# dac-v20_opamp.net
KiCad netlist of a schematic drawn in EAGLE
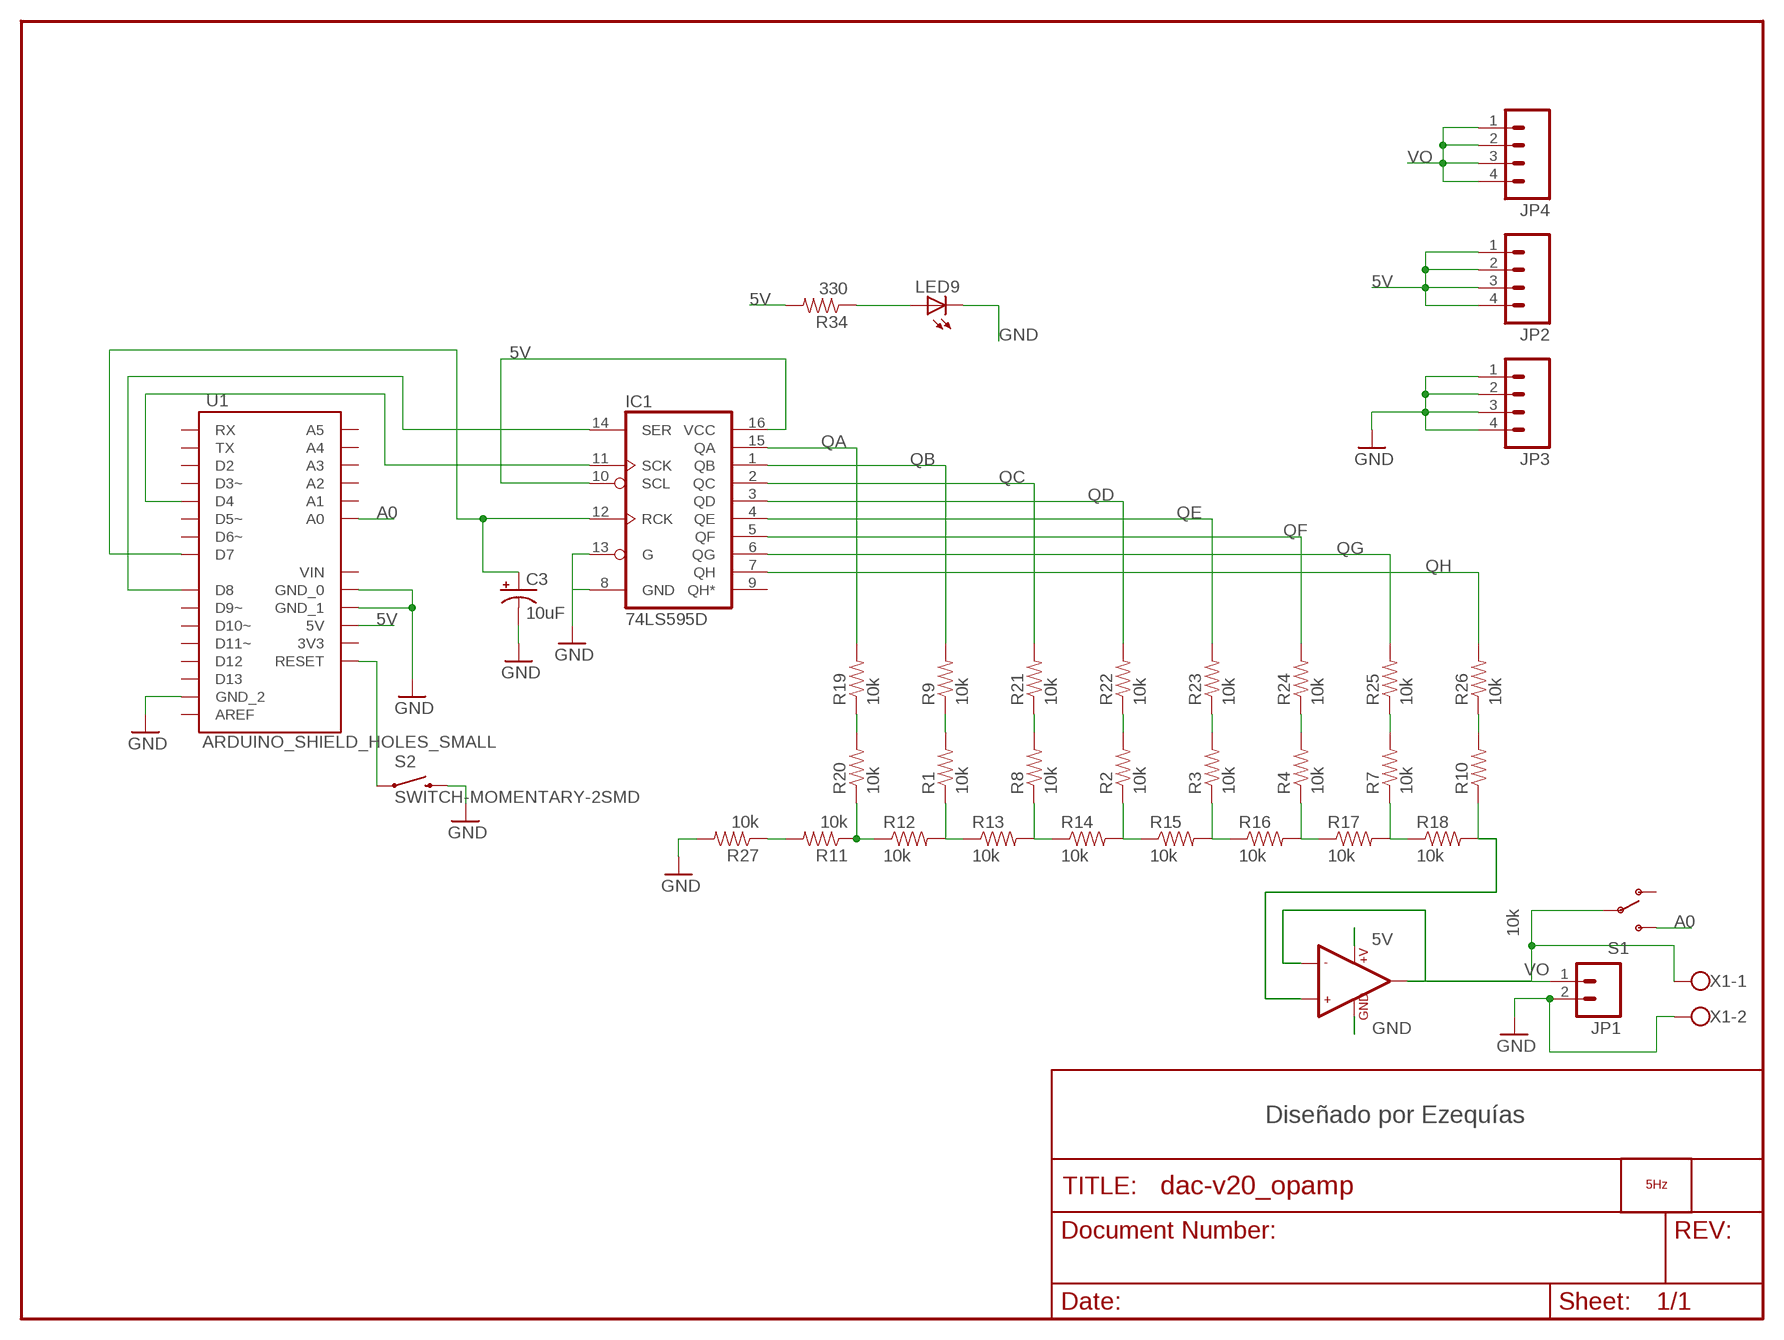
[diagram p0: schematic, sheet 1]

(export (version "E")
  (design (tool "Eeschema 10.0.6"))
  (components
    (comp (ref "C3")
      (value "10uF")
      (footprint "eagle-import:EIA3216")
      (libsource (lib "eagle-import") (part "CAP_POL1206"))
    )
    (comp (ref "IC1")
      (value "74LS595D")
      (footprint "eagle-import:SO16")
      (libsource (lib "eagle-import") (part "74595DLS"))
    )
    (comp (ref "JP1")
      (value "M02POLAR")
      (footprint "eagle-import:MOLEX-1X2")
      (libsource (lib "eagle-import") (part "M02POLAR"))
    )
    (comp (ref "JP2")
      (value "M04PTH")
      (footprint "eagle-import:1X04")
      (libsource (lib "eagle-import") (part "M04PTH"))
    )
    (comp (ref "JP3")
      (value "M04PTH")
      (footprint "eagle-import:1X04")
      (libsource (lib "eagle-import") (part "M04PTH"))
    )
    (comp (ref "JP4")
      (value "M04PTH")
      (footprint "eagle-import:1X04")
      (libsource (lib "eagle-import") (part "M04PTH"))
    )
    (comp (ref "LED9")
      (value "LED0603")
      (footprint "eagle-import:LED-0603")
      (libsource (lib "eagle-import") (part "LED0603"))
    )
    (comp (ref "LOGO2")
      (value "LOGO_5HZ_H_20MM")
      (footprint "eagle-import:5HZ_LOGO_H_20MM")
      (libsource (lib "eagle-import") (part "LOGO_5HZ_H_20MM"))
    )
    (comp (ref "R1")
      (value "10k")
      (footprint "eagle-import:0603-RES")
      (libsource (lib "eagle-import") (part "RESISTOR0603-RES"))
    )
    (comp (ref "R2")
      (value "10k")
      (footprint "eagle-import:0603-RES")
      (libsource (lib "eagle-import") (part "RESISTOR0603-RES"))
    )
    (comp (ref "R3")
      (value "10k")
      (footprint "eagle-import:0603-RES")
      (libsource (lib "eagle-import") (part "RESISTOR0603-RES"))
    )
    (comp (ref "R4")
      (value "10k")
      (footprint "eagle-import:0603-RES")
      (libsource (lib "eagle-import") (part "RESISTOR0603-RES"))
    )
    (comp (ref "R7")
      (value "10k")
      (footprint "eagle-import:0603-RES")
      (libsource (lib "eagle-import") (part "RESISTOR0603-RES"))
    )
    (comp (ref "R8")
      (value "10k")
      (footprint "eagle-import:0603-RES")
      (libsource (lib "eagle-import") (part "RESISTOR0603-RES"))
    )
    (comp (ref "R9")
      (value "10k")
      (footprint "eagle-import:0603-RES")
      (libsource (lib "eagle-import") (part "RESISTOR0603-RES"))
    )
    (comp (ref "R10")
      (value "10k")
      (footprint "eagle-import:0603-RES")
      (libsource (lib "eagle-import") (part "RESISTOR0603-RES"))
    )
    (comp (ref "R11")
      (value "10k")
      (footprint "eagle-import:0603-RES")
      (libsource (lib "eagle-import") (part "RESISTOR0603-RES"))
    )
    (comp (ref "R12")
      (value "10k")
      (footprint "eagle-import:0603-RES")
      (libsource (lib "eagle-import") (part "RESISTOR0603-RES"))
    )
    (comp (ref "R13")
      (value "10k")
      (footprint "eagle-import:0603-RES")
      (libsource (lib "eagle-import") (part "RESISTOR0603-RES"))
    )
    (comp (ref "R14")
      (value "10k")
      (footprint "eagle-import:0603-RES")
      (libsource (lib "eagle-import") (part "RESISTOR0603-RES"))
    )
    (comp (ref "R15")
      (value "10k")
      (footprint "eagle-import:0603-RES")
      (libsource (lib "eagle-import") (part "RESISTOR0603-RES"))
    )
    (comp (ref "R16")
      (value "10k")
      (footprint "eagle-import:0603-RES")
      (libsource (lib "eagle-import") (part "RESISTOR0603-RES"))
    )
    (comp (ref "R17")
      (value "10k")
      (footprint "eagle-import:0603-RES")
      (libsource (lib "eagle-import") (part "RESISTOR0603-RES"))
    )
    (comp (ref "R18")
      (value "10k")
      (footprint "eagle-import:0603-RES")
      (libsource (lib "eagle-import") (part "RESISTOR0603-RES"))
    )
    (comp (ref "R19")
      (value "10k")
      (footprint "eagle-import:0603-RES")
      (libsource (lib "eagle-import") (part "RESISTOR0603-RES"))
    )
    (comp (ref "R20")
      (value "10k")
      (footprint "eagle-import:0603-RES")
      (libsource (lib "eagle-import") (part "RESISTOR0603-RES"))
    )
    (comp (ref "R21")
      (value "10k")
      (footprint "eagle-import:0603-RES")
      (libsource (lib "eagle-import") (part "RESISTOR0603-RES"))
    )
    (comp (ref "R22")
      (value "10k")
      (footprint "eagle-import:0603-RES")
      (libsource (lib "eagle-import") (part "RESISTOR0603-RES"))
    )
    (comp (ref "R23")
      (value "10k")
      (footprint "eagle-import:0603-RES")
      (libsource (lib "eagle-import") (part "RESISTOR0603-RES"))
    )
    (comp (ref "R24")
      (value "10k")
      (footprint "eagle-import:0603-RES")
      (libsource (lib "eagle-import") (part "RESISTOR0603-RES"))
    )
    (comp (ref "R25")
      (value "10k")
      (footprint "eagle-import:0603-RES")
      (libsource (lib "eagle-import") (part "RESISTOR0603-RES"))
    )
    (comp (ref "R26")
      (value "10k")
      (footprint "eagle-import:0603-RES")
      (libsource (lib "eagle-import") (part "RESISTOR0603-RES"))
    )
    (comp (ref "R27")
      (value "10k")
      (footprint "eagle-import:0603-RES")
      (libsource (lib "eagle-import") (part "RESISTOR0603-RES"))
    )
    (comp (ref "R34")
      (value "330")
      (footprint "eagle-import:0603-RES")
      (libsource (lib "eagle-import") (part "RESISTOR0603-RES"))
    )
    (comp (ref "S1")
      (value "SWITCH-SPSTPTH")
      (footprint "eagle-import:SWITCH-SPDT")
      (libsource (lib "eagle-import") (part "SWITCH-SPSTPTH"))
    )
    (comp (ref "S2")
      (value "SWITCH-MOMENTARY-2SMD")
      (footprint "eagle-import:TACTILE_SWITCH_SMD")
      (libsource (lib "eagle-import") (part "SWITCH-MOMENTARY-2SMD"))
    )
    (comp (ref "U$1")
      (value "LMV358")
      (footprint "eagle-import:SO08")
      (libsource (lib "eagle-import") (part "LMV358"))
    )
    (comp (ref "U1")
      (value "ARDUINO_SHIELD_HOLES_SMALL")
      (footprint "eagle-import:UNO_SHIELD_SMALL_HOLES")
      (libsource (lib "eagle-import") (part "ARDUINO_SHIELD_HOLES_SMALL"))
    )
    (comp (ref "X1")
      (value "W237-102M2")
      (footprint "eagle-import:W237-102")
      (fields (field (name "MPN") "237-102"))
      (libsource (lib "eagle-import") (part "W237-102M2"))
    )
  )
  (nets
    (net (code "1") (name "/5V") (class "Default")
      (node (ref "IC1") (pin "10") (pinfunction "SCL_10") (pintype "input"))
      (node (ref "IC1") (pin "16") (pinfunction "VCC_16") (pintype "power_in"))
      (node (ref "JP2") (pin "1") (pinfunction "1_1") (pintype "passive"))
      (node (ref "JP2") (pin "2") (pinfunction "2_2") (pintype "passive"))
      (node (ref "JP2") (pin "3") (pinfunction "3_3") (pintype "passive"))
      (node (ref "JP2") (pin "4") (pinfunction "4_4") (pintype "passive"))
      (node (ref "R34") (pin "2") (pinfunction "2_2") (pintype "passive"))
      (node (ref "U$1") (pin "8") (pinfunction "+V_8") (pintype "power_in"))
      (node (ref "U1") (pin "5V") (pinfunction "5V_5V") (pintype "bidirectional"))
    )
    (net (code "2") (name "/A0") (class "Default")
      (node (ref "S1") (pin "3") (pinfunction "S_3") (pintype "passive"))
      (node (ref "U1") (pin "A0") (pinfunction "A0_A0") (pintype "bidirectional"))
    )
    (net (code "3") (name "/QA") (class "Default")
      (node (ref "IC1") (pin "15") (pinfunction "QA_15") (pintype "tri_state"))
      (node (ref "R19") (pin "2") (pinfunction "2_2") (pintype "passive"))
    )
    (net (code "4") (name "/QB") (class "Default")
      (node (ref "IC1") (pin "1") (pinfunction "QB_1") (pintype "tri_state"))
      (node (ref "R9") (pin "2") (pinfunction "2_2") (pintype "passive"))
    )
    (net (code "5") (name "/QC") (class "Default")
      (node (ref "IC1") (pin "2") (pinfunction "QC_2") (pintype "tri_state"))
      (node (ref "R21") (pin "2") (pinfunction "2_2") (pintype "passive"))
    )
    (net (code "6") (name "/QD") (class "Default")
      (node (ref "IC1") (pin "3") (pinfunction "QD_3") (pintype "tri_state"))
      (node (ref "R22") (pin "2") (pinfunction "2_2") (pintype "passive"))
    )
    (net (code "7") (name "/QE") (class "Default")
      (node (ref "IC1") (pin "4") (pinfunction "QE_4") (pintype "tri_state"))
      (node (ref "R23") (pin "2") (pinfunction "2_2") (pintype "passive"))
    )
    (net (code "8") (name "/QF") (class "Default")
      (node (ref "IC1") (pin "5") (pinfunction "QF_5") (pintype "tri_state"))
      (node (ref "R24") (pin "2") (pinfunction "2_2") (pintype "passive"))
    )
    (net (code "9") (name "/QG") (class "Default")
      (node (ref "IC1") (pin "6") (pinfunction "QG_6") (pintype "tri_state"))
      (node (ref "R25") (pin "2") (pinfunction "2_2") (pintype "passive"))
    )
    (net (code "10") (name "/QH") (class "Default")
      (node (ref "IC1") (pin "7") (pinfunction "QH_7") (pintype "tri_state"))
      (node (ref "R26") (pin "2") (pinfunction "2_2") (pintype "passive"))
    )
    (net (code "11") (name "/VO") (class "Default")
      (node (ref "JP1") (pin "1") (pinfunction "1_1") (pintype "passive"))
      (node (ref "JP4") (pin "1") (pinfunction "1_1") (pintype "passive"))
      (node (ref "JP4") (pin "2") (pinfunction "2_2") (pintype "passive"))
      (node (ref "JP4") (pin "3") (pinfunction "3_3") (pintype "passive"))
      (node (ref "JP4") (pin "4") (pinfunction "4_4") (pintype "passive"))
      (node (ref "S1") (pin "2") (pinfunction "P_2") (pintype "passive"))
      (node (ref "U$1") (pin "1") (pinfunction "OUT1_1") (pintype "output"))
      (node (ref "U$1") (pin "2") (pinfunction "-IN1_2") (pintype "input"))
      (node (ref "X1") (pin "1") (pinfunction "KL_1") (pintype "passive"))
    )
    (net (code "12") (name "GND") (class "Default")
      (node (ref "C3") (pin "C") (pinfunction "-_C") (pintype "passive"))
      (node (ref "IC1") (pin "13") (pinfunction "G_13") (pintype "input"))
      (node (ref "IC1") (pin "8") (pinfunction "GND_8") (pintype "power_in"))
      (node (ref "JP1") (pin "2") (pinfunction "2_2") (pintype "passive"))
      (node (ref "JP3") (pin "1") (pinfunction "1_1") (pintype "passive"))
      (node (ref "JP3") (pin "2") (pinfunction "2_2") (pintype "passive"))
      (node (ref "JP3") (pin "3") (pinfunction "3_3") (pintype "passive"))
      (node (ref "JP3") (pin "4") (pinfunction "4_4") (pintype "passive"))
      (node (ref "LED9") (pin "C") (pinfunction "C_C") (pintype "passive"))
      (node (ref "R27") (pin "2") (pinfunction "2_2") (pintype "passive"))
      (node (ref "S2") (pin "3") (pinfunction "2_3") (pintype "passive"))
      (node (ref "U$1") (pin "4") (pinfunction "GND_4") (pintype "power_in"))
      (node (ref "U1") (pin "GND_0") (pinfunction "GND_0_GND_0") (pintype "bidirectional"))
      (node (ref "U1") (pin "GND_1") (pinfunction "GND_1_GND_1") (pintype "bidirectional"))
      (node (ref "U1") (pin "GND_2") (pinfunction "GND_2_GND_2") (pintype "bidirectional"))
      (node (ref "X1") (pin "2") (pinfunction "KL_2") (pintype "passive"))
    )
    (net (code "13") (name "Net-(C3-+)") (class "Default")
      (node (ref "C3") (pin "A") (pinfunction "+_A") (pintype "passive"))
      (node (ref "IC1") (pin "12") (pinfunction "RCK_12") (pintype "input"))
      (node (ref "U1") (pin "D7") (pinfunction "D7_D7") (pintype "bidirectional"))
    )
    (net (code "14") (name "Net-(IC1-SCK)") (class "Default")
      (node (ref "IC1") (pin "11") (pinfunction "SCK_11") (pintype "input"))
      (node (ref "U1") (pin "D4") (pinfunction "D4_D4") (pintype "bidirectional"))
    )
    (net (code "15") (name "Net-(IC1-SER)") (class "Default")
      (node (ref "IC1") (pin "14") (pinfunction "SER_14") (pintype "input"))
      (node (ref "U1") (pin "D8") (pinfunction "D8_D8") (pintype "bidirectional"))
    )
    (net (code "16") (name "Net-(LED9-PadA)") (class "Default")
      (node (ref "LED9") (pin "A") (pinfunction "A_A") (pintype "passive"))
      (node (ref "R34") (pin "1") (pinfunction "1_1") (pintype "passive"))
    )
    (net (code "17") (name "Net-(R1-Pad1)") (class "Default")
      (node (ref "R1") (pin "1") (pinfunction "1_1") (pintype "passive"))
      (node (ref "R12") (pin "2") (pinfunction "2_2") (pintype "passive"))
      (node (ref "R13") (pin "1") (pinfunction "1_1") (pintype "passive"))
    )
    (net (code "18") (name "Net-(R1-Pad2)") (class "Default")
      (node (ref "R1") (pin "2") (pinfunction "2_2") (pintype "passive"))
      (node (ref "R9") (pin "1") (pinfunction "1_1") (pintype "passive"))
    )
    (net (code "19") (name "Net-(R2-Pad2)") (class "Default")
      (node (ref "R2") (pin "2") (pinfunction "2_2") (pintype "passive"))
      (node (ref "R22") (pin "1") (pinfunction "1_1") (pintype "passive"))
    )
    (net (code "20") (name "Net-(R10-Pad2)") (class "Default")
      (node (ref "R10") (pin "2") (pinfunction "2_2") (pintype "passive"))
      (node (ref "R26") (pin "1") (pinfunction "1_1") (pintype "passive"))
    )
    (net (code "21") (name "Net-(R11-Pad1)") (class "Default")
      (node (ref "R11") (pin "1") (pinfunction "1_1") (pintype "passive"))
      (node (ref "R12") (pin "1") (pinfunction "1_1") (pintype "passive"))
      (node (ref "R20") (pin "1") (pinfunction "1_1") (pintype "passive"))
    )
    (net (code "22") (name "Net-(R11-Pad2)") (class "Default")
      (node (ref "R11") (pin "2") (pinfunction "2_2") (pintype "passive"))
      (node (ref "R27") (pin "1") (pinfunction "1_1") (pintype "passive"))
    )
    (net (code "23") (name "Net-(R13-Pad2)") (class "Default")
      (node (ref "R13") (pin "2") (pinfunction "2_2") (pintype "passive"))
      (node (ref "R14") (pin "1") (pinfunction "1_1") (pintype "passive"))
      (node (ref "R8") (pin "1") (pinfunction "1_1") (pintype "passive"))
    )
    (net (code "24") (name "Net-(R14-Pad2)") (class "Default")
      (node (ref "R14") (pin "2") (pinfunction "2_2") (pintype "passive"))
      (node (ref "R15") (pin "1") (pinfunction "1_1") (pintype "passive"))
      (node (ref "R2") (pin "1") (pinfunction "1_1") (pintype "passive"))
    )
    (net (code "25") (name "Net-(R15-Pad2)") (class "Default")
      (node (ref "R15") (pin "2") (pinfunction "2_2") (pintype "passive"))
      (node (ref "R16") (pin "1") (pinfunction "1_1") (pintype "passive"))
      (node (ref "R3") (pin "1") (pinfunction "1_1") (pintype "passive"))
    )
    (net (code "26") (name "Net-(R16-Pad2)") (class "Default")
      (node (ref "R16") (pin "2") (pinfunction "2_2") (pintype "passive"))
      (node (ref "R17") (pin "1") (pinfunction "1_1") (pintype "passive"))
      (node (ref "R4") (pin "1") (pinfunction "1_1") (pintype "passive"))
    )
    (net (code "27") (name "Net-(R17-Pad2)") (class "Default")
      (node (ref "R17") (pin "2") (pinfunction "2_2") (pintype "passive"))
      (node (ref "R18") (pin "1") (pinfunction "1_1") (pintype "passive"))
      (node (ref "R7") (pin "1") (pinfunction "1_1") (pintype "passive"))
    )
    (net (code "28") (name "Net-(R19-Pad1)") (class "Default")
      (node (ref "R19") (pin "1") (pinfunction "1_1") (pintype "passive"))
      (node (ref "R20") (pin "2") (pinfunction "2_2") (pintype "passive"))
    )
    (net (code "29") (name "Net-(R21-Pad1)") (class "Default")
      (node (ref "R21") (pin "1") (pinfunction "1_1") (pintype "passive"))
      (node (ref "R8") (pin "2") (pinfunction "2_2") (pintype "passive"))
    )
    (net (code "30") (name "Net-(R23-Pad1)") (class "Default")
      (node (ref "R23") (pin "1") (pinfunction "1_1") (pintype "passive"))
      (node (ref "R3") (pin "2") (pinfunction "2_2") (pintype "passive"))
    )
    (net (code "31") (name "Net-(R24-Pad1)") (class "Default")
      (node (ref "R24") (pin "1") (pinfunction "1_1") (pintype "passive"))
      (node (ref "R4") (pin "2") (pinfunction "2_2") (pintype "passive"))
    )
    (net (code "32") (name "Net-(R25-Pad1)") (class "Default")
      (node (ref "R25") (pin "1") (pinfunction "1_1") (pintype "passive"))
      (node (ref "R7") (pin "2") (pinfunction "2_2") (pintype "passive"))
    )
    (net (code "33") (name "Net-(U$1A-+IN1)") (class "Default")
      (node (ref "R10") (pin "1") (pinfunction "1_1") (pintype "passive"))
      (node (ref "R18") (pin "2") (pinfunction "2_2") (pintype "passive"))
      (node (ref "U$1") (pin "3") (pinfunction "+IN1_3") (pintype "input"))
    )
    (net (code "34") (name "Net-(U1-RESET)") (class "Default")
      (node (ref "S2") (pin "1") (pinfunction "1_1") (pintype "passive"))
      (node (ref "U1") (pin "RES") (pinfunction "RESET_RES") (pintype "bidirectional"))
    )
    (net (code "35") (name "unconnected-(IC1-QH*-Pad9)") (class "Default")
      (node (ref "IC1") (pin "9") (pinfunction "QH*_9") (pintype "tri_state"))
    )
    (net (code "36") (name "unconnected-(S1-O-Pad1)") (class "Default")
      (node (ref "S1") (pin "1") (pinfunction "O_1") (pintype "passive"))
    )
    (net (code "37") (name "unconnected-(U1-3V3-Pad3.3V)") (class "Default")
      (node (ref "U1") (pin "3.3V") (pinfunction "3V3_3.3V") (pintype "bidirectional"))
    )
    (net (code "38") (name "unconnected-(U1-D3~{}-PadD3)") (class "Default")
      (node (ref "U1") (pin "D3") (pinfunction "D3~{}_D3") (pintype "bidirectional"))
    )
    (net (code "39") (name "unconnected-(U1-D5~{}-PadD5)") (class "Default")
      (node (ref "U1") (pin "D5") (pinfunction "D5~{}_D5") (pintype "bidirectional"))
    )
    (net (code "40") (name "unconnected-(U1-D6~{}-PadD6)") (class "Default")
      (node (ref "U1") (pin "D6") (pinfunction "D6~{}_D6") (pintype "bidirectional"))
    )
    (net (code "41") (name "unconnected-(U1-D9~{}-PadD9)") (class "Default")
      (node (ref "U1") (pin "D9") (pinfunction "D9~{}_D9") (pintype "bidirectional"))
    )
    (net (code "42") (name "unconnected-(U1-D10~{}-PadD10)") (class "Default")
      (node (ref "U1") (pin "D10") (pinfunction "D10~{}_D10") (pintype "bidirectional"))
    )
    (net (code "43") (name "unconnected-(U1-D11~{}-PadD11)") (class "Default")
      (node (ref "U1") (pin "D11") (pinfunction "D11~{}_D11") (pintype "bidirectional"))
    )
    (net (code "44") (name "unconnected-(U1-PadA1)") (class "Default")
      (node (ref "U1") (pin "A1") (pinfunction "A1_A1") (pintype "bidirectional"))
    )
    (net (code "45") (name "unconnected-(U1-PadA2)") (class "Default")
      (node (ref "U1") (pin "A2") (pinfunction "A2_A2") (pintype "bidirectional"))
    )
    (net (code "46") (name "unconnected-(U1-PadA3)") (class "Default")
      (node (ref "U1") (pin "A3") (pinfunction "A3_A3") (pintype "bidirectional"))
    )
    (net (code "47") (name "unconnected-(U1-PadA4)") (class "Default")
      (node (ref "U1") (pin "A4") (pinfunction "A4_A4") (pintype "bidirectional"))
    )
    (net (code "48") (name "unconnected-(U1-PadA5)") (class "Default")
      (node (ref "U1") (pin "A5") (pinfunction "A5_A5") (pintype "bidirectional"))
    )
    (net (code "49") (name "unconnected-(U1-PadAREF)") (class "Default")
      (node (ref "U1") (pin "AREF") (pinfunction "AREF_AREF") (pintype "bidirectional"))
    )
    (net (code "50") (name "unconnected-(U1-PadD2)") (class "Default")
      (node (ref "U1") (pin "D2") (pinfunction "D2_D2") (pintype "bidirectional"))
    )
    (net (code "51") (name "unconnected-(U1-PadD12)") (class "Default")
      (node (ref "U1") (pin "D12") (pinfunction "D12_D12") (pintype "bidirectional"))
    )
    (net (code "52") (name "unconnected-(U1-PadD13)") (class "Default")
      (node (ref "U1") (pin "D13") (pinfunction "D13_D13") (pintype "bidirectional"))
    )
    (net (code "53") (name "unconnected-(U1-PadRX)") (class "Default")
      (node (ref "U1") (pin "RX") (pinfunction "RX_RX") (pintype "bidirectional"))
    )
    (net (code "54") (name "unconnected-(U1-PadTX)") (class "Default")
      (node (ref "U1") (pin "TX") (pinfunction "TX_TX") (pintype "bidirectional"))
    )
    (net (code "55") (name "unconnected-(U1-PadVIN)") (class "Default")
      (node (ref "U1") (pin "VIN") (pinfunction "VIN_VIN") (pintype "bidirectional"))
    )
  )
)
